# Wifi.net
KiCad netlist of a schematic drawn in EAGLE
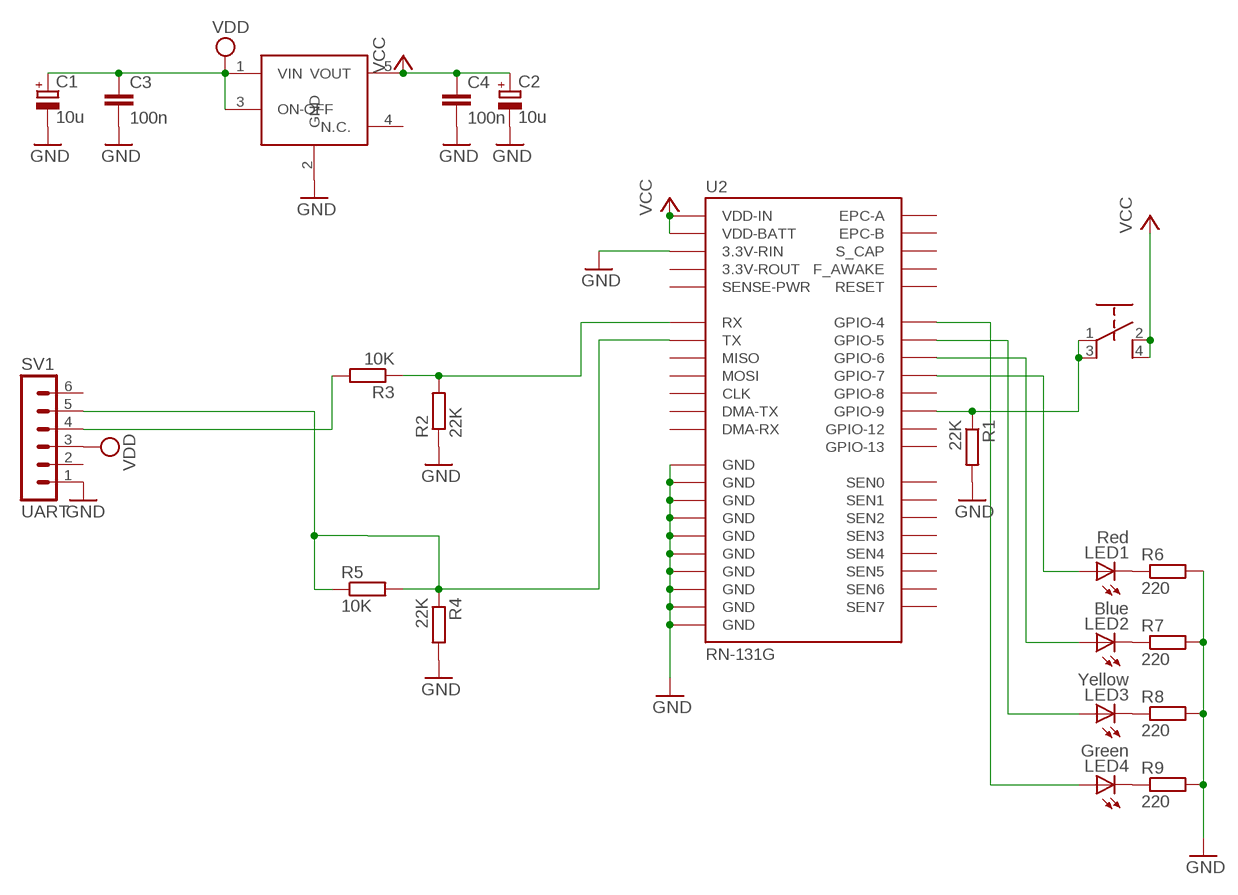
[diagram p0: schematic, sheet 1]

(export (version "E")
  (design (tool "Eeschema 10.0.6"))
  (components
    (comp (ref "C1")
      (value "10u")
      (footprint "eagle-import:A_3216-18W")
      (libsource (lib "eagle-import") (part "CPOL-EUA/3216-18W"))
    )
    (comp (ref "C2")
      (value "10u")
      (footprint "eagle-import:A_3216-18W")
      (libsource (lib "eagle-import") (part "CPOL-EUA/3216-18W"))
    )
    (comp (ref "C3")
      (value "100n")
      (footprint "eagle-import:C0805")
      (libsource (lib "eagle-import") (part "C-EUC0805"))
    )
    (comp (ref "C4")
      (value "100n")
      (footprint "eagle-import:C0805")
      (libsource (lib "eagle-import") (part "C-EUC0805"))
    )
    (comp (ref "LED1")
      (value "Red")
      (footprint "eagle-import:LED3MM")
      (libsource (lib "eagle-import") (part "LED3MM"))
    )
    (comp (ref "LED2")
      (value "Blue")
      (footprint "eagle-import:LED3MM")
      (libsource (lib "eagle-import") (part "LED3MM"))
    )
    (comp (ref "LED3")
      (value "Yellow")
      (footprint "eagle-import:LED3MM")
      (libsource (lib "eagle-import") (part "LED3MM"))
    )
    (comp (ref "LED4")
      (value "Green")
      (footprint "eagle-import:LED3MM")
      (libsource (lib "eagle-import") (part "LED3MM"))
    )
    (comp (ref "R1")
      (value "22K")
      (footprint "eagle-import:R0805")
      (libsource (lib "eagle-import") (part "R-EU_R0805"))
    )
    (comp (ref "R2")
      (value "22K")
      (footprint "eagle-import:R0805")
      (libsource (lib "eagle-import") (part "R-EU_R0805"))
    )
    (comp (ref "R3")
      (value "10K")
      (footprint "eagle-import:R0805")
      (libsource (lib "eagle-import") (part "R-EU_R0805"))
    )
    (comp (ref "R4")
      (value "22K")
      (footprint "eagle-import:R0805")
      (libsource (lib "eagle-import") (part "R-EU_R0805"))
    )
    (comp (ref "R5")
      (value "10K")
      (footprint "eagle-import:R0805")
      (libsource (lib "eagle-import") (part "R-EU_R0805"))
    )
    (comp (ref "R6")
      (value "220")
      (footprint "eagle-import:R0805")
      (libsource (lib "eagle-import") (part "R-EU_R0805"))
    )
    (comp (ref "R7")
      (value "220")
      (footprint "eagle-import:R0805")
      (libsource (lib "eagle-import") (part "R-EU_R0805"))
    )
    (comp (ref "R8")
      (value "220")
      (footprint "eagle-import:R0805")
      (libsource (lib "eagle-import") (part "R-EU_R0805"))
    )
    (comp (ref "R9")
      (value "220")
      (footprint "eagle-import:R0805")
      (libsource (lib "eagle-import") (part "R-EU_R0805"))
    )
    (comp (ref "S2")
      (value "PUSHBUTTON")
      (footprint "eagle-import:PUSHBUTTON")
      (libsource (lib "eagle-import") (part "PUSHBUTTON"))
    )
    (comp (ref "SV1")
      (value "UART")
      (footprint "eagle-import:MA06-1")
      (libsource (lib "eagle-import") (part "MA06-1"))
    )
    (comp (ref "U1")
      (value "LP2985")
      (footprint "eagle-import:SOT23-5")
      (libsource (lib "eagle-import") (part "LP2985"))
    )
    (comp (ref "U2")
      (value "RN-131G")
      (footprint "eagle-import:RN-131G")
      (libsource (lib "eagle-import") (part "RN-131G"))
    )
  )
  (nets
    (net (code "1") (name "GND") (class "Default")
      (node (ref "C1") (pin "-") (pinfunction "-_-") (pintype "passive"))
      (node (ref "C2") (pin "-") (pinfunction "-_-") (pintype "passive"))
      (node (ref "C3") (pin "2") (pinfunction "2_2") (pintype "passive"))
      (node (ref "C4") (pin "2") (pinfunction "2_2") (pintype "passive"))
      (node (ref "R1") (pin "2") (pinfunction "2_2") (pintype "passive"))
      (node (ref "R2") (pin "1") (pinfunction "1_1") (pintype "passive"))
      (node (ref "R4") (pin "2") (pinfunction "2_2") (pintype "passive"))
      (node (ref "R6") (pin "2") (pinfunction "2_2") (pintype "passive"))
      (node (ref "R7") (pin "2") (pinfunction "2_2") (pintype "passive"))
      (node (ref "R8") (pin "2") (pinfunction "2_2") (pintype "passive"))
      (node (ref "R9") (pin "2") (pinfunction "2_2") (pintype "passive"))
      (node (ref "SV1") (pin "1") (pinfunction "1_1") (pintype "passive"))
      (node (ref "U1") (pin "2") (pinfunction "GND_2") (pintype "bidirectional"))
      (node (ref "U2") (pin "P$18") (pinfunction "3.3V-RIN_P$18") (pintype "bidirectional"))
      (node (ref "U2") (pin "P$19") (pinfunction "GND_P$19") (pintype "bidirectional"))
      (node (ref "U2") (pin "P$36") (pinfunction "GND_P$36") (pintype "bidirectional"))
      (node (ref "U2") (pin "P$37") (pinfunction "GND_P$37") (pintype "bidirectional"))
      (node (ref "U2") (pin "P$38") (pinfunction "GND_P$38") (pintype "bidirectional"))
      (node (ref "U2") (pin "P$39") (pinfunction "GND_P$39") (pintype "bidirectional"))
      (node (ref "U2") (pin "P$40") (pinfunction "GND_P$40") (pintype "bidirectional"))
      (node (ref "U2") (pin "P$41") (pinfunction "GND_P$41") (pintype "bidirectional"))
      (node (ref "U2") (pin "P$42") (pinfunction "GND_P$42") (pintype "bidirectional"))
      (node (ref "U2") (pin "P$43") (pinfunction "GND_P$43") (pintype "bidirectional"))
      (node (ref "U2") (pin "P$44") (pinfunction "GND_P$44") (pintype "bidirectional"))
    )
    (net (code "2") (name "Net-(LED1-C)") (class "Default")
      (node (ref "LED1") (pin "K") (pinfunction "C_K") (pintype "passive"))
      (node (ref "R6") (pin "1") (pinfunction "1_1") (pintype "passive"))
    )
    (net (code "3") (name "Net-(LED2-C)") (class "Default")
      (node (ref "LED2") (pin "K") (pinfunction "C_K") (pintype "passive"))
      (node (ref "R7") (pin "1") (pinfunction "1_1") (pintype "passive"))
    )
    (net (code "4") (name "Net-(LED3-C)") (class "Default")
      (node (ref "LED3") (pin "K") (pinfunction "C_K") (pintype "passive"))
      (node (ref "R8") (pin "1") (pinfunction "1_1") (pintype "passive"))
    )
    (net (code "5") (name "Net-(LED4-C)") (class "Default")
      (node (ref "LED4") (pin "K") (pinfunction "C_K") (pintype "passive"))
      (node (ref "R9") (pin "1") (pinfunction "1_1") (pintype "passive"))
    )
    (net (code "6") (name "Net-(R3-Pad2)") (class "Default")
      (node (ref "R3") (pin "2") (pinfunction "2_2") (pintype "passive"))
      (node (ref "SV1") (pin "4") (pinfunction "4_4") (pintype "passive"))
    )
    (net (code "7") (name "Net-(U2-GPIO-4)") (class "Default")
      (node (ref "LED4") (pin "A") (pinfunction "A_A") (pintype "passive"))
      (node (ref "U2") (pin "P$29") (pinfunction "GPIO-4_P$29") (pintype "bidirectional"))
    )
    (net (code "8") (name "Net-(U2-GPIO-5)") (class "Default")
      (node (ref "LED3") (pin "A") (pinfunction "A_A") (pintype "passive"))
      (node (ref "U2") (pin "P$28") (pinfunction "GPIO-5_P$28") (pintype "bidirectional"))
    )
    (net (code "9") (name "Net-(U2-GPIO-6)") (class "Default")
      (node (ref "LED2") (pin "A") (pinfunction "A_A") (pintype "passive"))
      (node (ref "U2") (pin "P$27") (pinfunction "GPIO-6_P$27") (pintype "bidirectional"))
    )
    (net (code "10") (name "Net-(U2-GPIO-7)") (class "Default")
      (node (ref "LED1") (pin "A") (pinfunction "A_A") (pintype "passive"))
      (node (ref "U2") (pin "P$26") (pinfunction "GPIO-7_P$26") (pintype "bidirectional"))
    )
    (net (code "11") (name "Net-(U2-GPIO-9)") (class "Default")
      (node (ref "R1") (pin "1") (pinfunction "1_1") (pintype "passive"))
      (node (ref "S2") (pin "1") (pinfunction "1_1") (pintype "bidirectional"))
      (node (ref "S2") (pin "3") (pinfunction "3_3") (pintype "bidirectional"))
      (node (ref "U2") (pin "P$24") (pinfunction "GPIO-9_P$24") (pintype "bidirectional"))
    )
    (net (code "12") (name "Net-(U2-RX)") (class "Default")
      (node (ref "R2") (pin "2") (pinfunction "2_2") (pintype "passive"))
      (node (ref "R3") (pin "1") (pinfunction "1_1") (pintype "passive"))
      (node (ref "U2") (pin "P$12") (pinfunction "RX_P$12") (pintype "bidirectional"))
    )
    (net (code "13") (name "Net-(U2-TX)") (class "Default")
      (node (ref "R4") (pin "1") (pinfunction "1_1") (pintype "passive"))
      (node (ref "R5") (pin "1") (pinfunction "1_1") (pintype "passive"))
      (node (ref "R5") (pin "2") (pinfunction "2_2") (pintype "passive"))
      (node (ref "SV1") (pin "5") (pinfunction "5_5") (pintype "passive"))
      (node (ref "U2") (pin "P$13") (pinfunction "TX_P$13") (pintype "bidirectional"))
    )
    (net (code "14") (name "VCC") (class "Default")
      (node (ref "C2") (pin "+") (pinfunction "+_+") (pintype "passive"))
      (node (ref "C4") (pin "1") (pinfunction "1_1") (pintype "passive"))
      (node (ref "S2") (pin "2") (pinfunction "2_2") (pintype "bidirectional"))
      (node (ref "S2") (pin "4") (pinfunction "4_4") (pintype "bidirectional"))
      (node (ref "U1") (pin "5") (pinfunction "VOUT_5") (pintype "bidirectional"))
      (node (ref "U2") (pin "P$20") (pinfunction "VDD-BATT_P$20") (pintype "bidirectional"))
      (node (ref "U2") (pin "P$21") (pinfunction "VDD-IN_P$21") (pintype "bidirectional"))
    )
    (net (code "15") (name "VDD") (class "Default")
      (node (ref "C1") (pin "+") (pinfunction "+_+") (pintype "passive"))
      (node (ref "C3") (pin "1") (pinfunction "1_1") (pintype "passive"))
      (node (ref "SV1") (pin "3") (pinfunction "3_3") (pintype "passive"))
      (node (ref "U1") (pin "1") (pinfunction "VIN_1") (pintype "bidirectional"))
      (node (ref "U1") (pin "3") (pinfunction "ON-OFF_3") (pintype "bidirectional"))
    )
    (net (code "16") (name "unconnected-(SV1-Pad2)") (class "Default")
      (node (ref "SV1") (pin "2") (pinfunction "2_2") (pintype "passive"))
    )
    (net (code "17") (name "unconnected-(SV1-Pad6)") (class "Default")
      (node (ref "SV1") (pin "6") (pinfunction "6_6") (pintype "passive"))
    )
    (net (code "18") (name "unconnected-(U1-N.C.-Pad4)") (class "Default")
      (node (ref "U1") (pin "4") (pinfunction "N.C._4") (pintype "bidirectional"))
    )
    (net (code "19") (name "unconnected-(U2-3.3V-ROUT-PadP$17)") (class "Default")
      (node (ref "U2") (pin "P$17") (pinfunction "3.3V-ROUT_P$17") (pintype "bidirectional"))
    )
    (net (code "20") (name "unconnected-(U2-CLK-PadP$15)") (class "Default")
      (node (ref "U2") (pin "P$15") (pinfunction "CLK_P$15") (pintype "bidirectional"))
    )
    (net (code "21") (name "unconnected-(U2-DMA-RX-PadP$23)") (class "Default")
      (node (ref "U2") (pin "P$23") (pinfunction "DMA-RX_P$23") (pintype "bidirectional"))
    )
    (net (code "22") (name "unconnected-(U2-DMA-TX-PadP$22)") (class "Default")
      (node (ref "U2") (pin "P$22") (pinfunction "DMA-TX_P$22") (pintype "bidirectional"))
    )
    (net (code "23") (name "unconnected-(U2-EPC-A-PadP$6)") (class "Default")
      (node (ref "U2") (pin "P$6") (pinfunction "EPC-A_P$6") (pintype "bidirectional"))
    )
    (net (code "24") (name "unconnected-(U2-EPC-B-PadP$7)") (class "Default")
      (node (ref "U2") (pin "P$7") (pinfunction "EPC-B_P$7") (pintype "bidirectional"))
    )
    (net (code "25") (name "unconnected-(U2-F_AWAKE-PadP$9)") (class "Default")
      (node (ref "U2") (pin "P$9") (pinfunction "F_AWAKE_P$9") (pintype "bidirectional"))
    )
    (net (code "26") (name "unconnected-(U2-GPIO-8-PadP$25)") (class "Default")
      (node (ref "U2") (pin "P$25") (pinfunction "GPIO-8_P$25") (pintype "bidirectional"))
    )
    (net (code "27") (name "unconnected-(U2-GPIO-12-PadP$11)") (class "Default")
      (node (ref "U2") (pin "P$11") (pinfunction "GPIO-12_P$11") (pintype "bidirectional"))
    )
    (net (code "28") (name "unconnected-(U2-GPIO-13-PadP$10)") (class "Default")
      (node (ref "U2") (pin "P$10") (pinfunction "GPIO-13_P$10") (pintype "bidirectional"))
    )
    (net (code "29") (name "unconnected-(U2-MISO-PadP$16)") (class "Default")
      (node (ref "U2") (pin "P$16") (pinfunction "MISO_P$16") (pintype "bidirectional"))
    )
    (net (code "30") (name "unconnected-(U2-MOSI-PadP$14)") (class "Default")
      (node (ref "U2") (pin "P$14") (pinfunction "MOSI_P$14") (pintype "bidirectional"))
    )
    (net (code "31") (name "unconnected-(U2-RESET-PadP$5)") (class "Default")
      (node (ref "U2") (pin "P$5") (pinfunction "RESET_P$5") (pintype "bidirectional"))
    )
    (net (code "32") (name "unconnected-(U2-SEN0-PadP$34)") (class "Default")
      (node (ref "U2") (pin "P$34") (pinfunction "SEN0_P$34") (pintype "bidirectional"))
    )
    (net (code "33") (name "unconnected-(U2-SEN1-PadP$30)") (class "Default")
      (node (ref "U2") (pin "P$30") (pinfunction "SEN1_P$30") (pintype "bidirectional"))
    )
    (net (code "34") (name "unconnected-(U2-SEN2-PadP$31)") (class "Default")
      (node (ref "U2") (pin "P$31") (pinfunction "SEN2_P$31") (pintype "bidirectional"))
    )
    (net (code "35") (name "unconnected-(U2-SEN3-PadP$32)") (class "Default")
      (node (ref "U2") (pin "P$32") (pinfunction "SEN3_P$32") (pintype "bidirectional"))
    )
    (net (code "36") (name "unconnected-(U2-SEN4-PadP$2)") (class "Default")
      (node (ref "U2") (pin "P$2") (pinfunction "SEN4_P$2") (pintype "bidirectional"))
    )
    (net (code "37") (name "unconnected-(U2-SEN5-PadP$3)") (class "Default")
      (node (ref "U2") (pin "P$3") (pinfunction "SEN5_P$3") (pintype "bidirectional"))
    )
    (net (code "38") (name "unconnected-(U2-SEN6-PadP$1)") (class "Default")
      (node (ref "U2") (pin "P$1") (pinfunction "SEN6_P$1") (pintype "bidirectional"))
    )
    (net (code "39") (name "unconnected-(U2-SEN7-PadP$4)") (class "Default")
      (node (ref "U2") (pin "P$4") (pinfunction "SEN7_P$4") (pintype "bidirectional"))
    )
    (net (code "40") (name "unconnected-(U2-SENSE-PWR-PadP$33)") (class "Default")
      (node (ref "U2") (pin "P$33") (pinfunction "SENSE-PWR_P$33") (pintype "bidirectional"))
    )
    (net (code "41") (name "unconnected-(U2-S_CAP-PadP$8)") (class "Default")
      (node (ref "U2") (pin "P$8") (pinfunction "S_CAP_P$8") (pintype "bidirectional"))
    )
  )
)
